# M660A.net
KiCad netlist of a schematic drawn in EAGLE
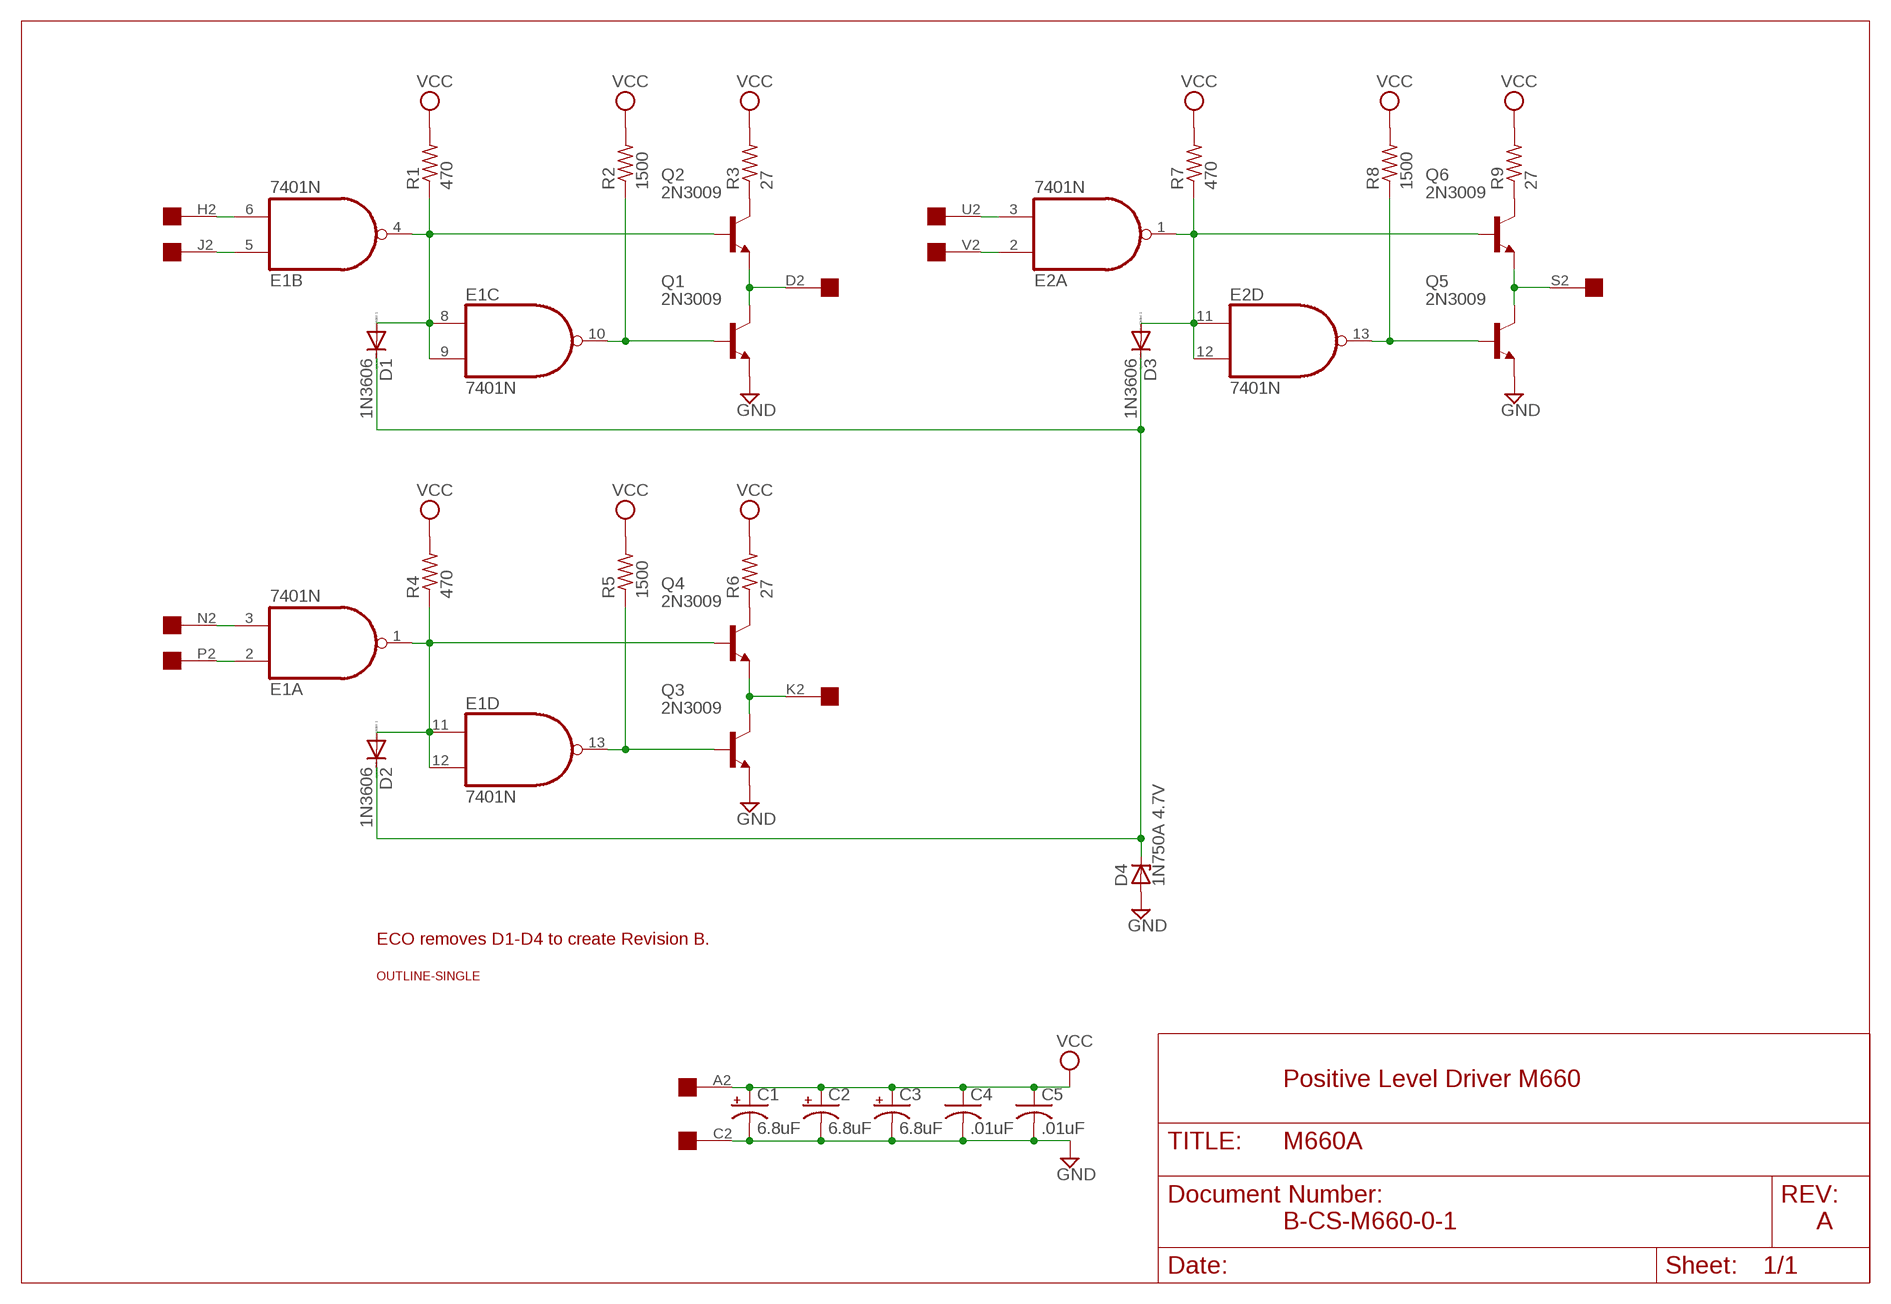
[diagram p0: schematic, sheet 1]

(export (version "E")
  (design (tool "Eeschema 10.0.6"))
  (components
    (comp (ref "C1")
      (value "6.8uF")
      (footprint "eagle-import:E15-5")
      (libsource (lib "eagle-import") (part "CPOL-USE15-5AXIAL"))
    )
    (comp (ref "C2")
      (value "6.8uF")
      (footprint "eagle-import:E15-5")
      (libsource (lib "eagle-import") (part "CPOL-USE15-5AXIAL"))
    )
    (comp (ref "C3")
      (value "6.8uF")
      (footprint "eagle-import:E15-5")
      (libsource (lib "eagle-import") (part "CPOL-USE15-5AXIAL"))
    )
    (comp (ref "C4")
      (value ".01uF")
      (footprint "eagle-import:C050-025X075")
      (libsource (lib "eagle-import") (part "C-US050-025X075"))
    )
    (comp (ref "C5")
      (value ".01uF")
      (footprint "eagle-import:C050-025X075")
      (libsource (lib "eagle-import") (part "C-US050-025X075"))
    )
    (comp (ref "D1")
      (value "1N3606")
      (footprint "eagle-import:DO35-10")
      (libsource (lib "eagle-import") (part "1N4148DO35-10"))
    )
    (comp (ref "D2")
      (value "1N3606")
      (footprint "eagle-import:DO35-10")
      (libsource (lib "eagle-import") (part "1N4148DO35-10"))
    )
    (comp (ref "D3")
      (value "1N3606")
      (footprint "eagle-import:DO35-10")
      (libsource (lib "eagle-import") (part "1N4148DO35-10"))
    )
    (comp (ref "D4")
      (value "1N750A 4.7V")
      (footprint "eagle-import:DO35Z10")
      (libsource (lib "eagle-import") (part "ZENER-DIODEDO35Z10"))
    )
    (comp (ref "E1")
      (value "7401N")
      (footprint "eagle-import:DIL14")
      (libsource (lib "eagle-import") (part "7401NLS"))
    )
    (comp (ref "E2")
      (value "7401N")
      (footprint "eagle-import:DIL14")
      (libsource (lib "eagle-import") (part "7401NLS"))
    )
    (comp (ref "Q1")
      (value "2N3009")
      (footprint "eagle-import:TO5")
      (libsource (lib "eagle-import") (part "2N2219"))
    )
    (comp (ref "Q2")
      (value "2N3009")
      (footprint "eagle-import:TO5")
      (libsource (lib "eagle-import") (part "2N2219"))
    )
    (comp (ref "Q3")
      (value "2N3009")
      (footprint "eagle-import:TO5")
      (libsource (lib "eagle-import") (part "2N2219"))
    )
    (comp (ref "Q4")
      (value "2N3009")
      (footprint "eagle-import:TO5")
      (libsource (lib "eagle-import") (part "2N2219"))
    )
    (comp (ref "Q5")
      (value "2N3009")
      (footprint "eagle-import:TO5")
      (libsource (lib "eagle-import") (part "2N2219"))
    )
    (comp (ref "Q6")
      (value "2N3009")
      (footprint "eagle-import:TO5")
      (libsource (lib "eagle-import") (part "2N2219"))
    )
    (comp (ref "R1")
      (value "470")
      (footprint "eagle-import:0207_10")
      (libsource (lib "eagle-import") (part "R-US_0207/10"))
    )
    (comp (ref "R2")
      (value "1500")
      (footprint "eagle-import:0207_10")
      (libsource (lib "eagle-import") (part "R-US_0207/10"))
    )
    (comp (ref "R3")
      (value "27")
      (footprint "eagle-import:0411_15")
      (libsource (lib "eagle-import") (part "R-US_0411/15"))
    )
    (comp (ref "R4")
      (value "470")
      (footprint "eagle-import:0207_10")
      (libsource (lib "eagle-import") (part "R-US_0207/10"))
    )
    (comp (ref "R5")
      (value "1500")
      (footprint "eagle-import:0207_10")
      (libsource (lib "eagle-import") (part "R-US_0207/10"))
    )
    (comp (ref "R6")
      (value "27")
      (footprint "eagle-import:0411_15")
      (libsource (lib "eagle-import") (part "R-US_0411/15"))
    )
    (comp (ref "R7")
      (value "470")
      (footprint "eagle-import:0207_10")
      (libsource (lib "eagle-import") (part "R-US_0207/10"))
    )
    (comp (ref "R8")
      (value "1500")
      (footprint "eagle-import:0207_10")
      (libsource (lib "eagle-import") (part "R-US_0207/10"))
    )
    (comp (ref "R9")
      (value "27")
      (footprint "eagle-import:0411_15")
      (libsource (lib "eagle-import") (part "R-US_0411/15"))
    )
    (comp (ref "U$1")
      (value "OUTLINE-SINGLE")
      (footprint "eagle-import:SINGLE")
      (libsource (lib "eagle-import") (part "OUTLINE-SINGLE"))
    )
    (comp (ref "U$3")
      (value "EDGE-1")
      (footprint "eagle-import:EDGE-CON1")
      (libsource (lib "eagle-import") (part "EDGE-1"))
    )
  )
  (nets
    (net (code "1") (name "GND") (class "Default")
      (node (ref "C1") (pin "-") (pinfunction "-_-") (pintype "passive"))
      (node (ref "C2") (pin "-") (pinfunction "-_-") (pintype "passive"))
      (node (ref "C3") (pin "-") (pinfunction "-_-") (pintype "passive"))
      (node (ref "C4") (pin "2") (pinfunction "2_2") (pintype "passive"))
      (node (ref "C5") (pin "2") (pinfunction "2_2") (pintype "passive"))
      (node (ref "D4") (pin "A") (pinfunction "A_A") (pintype "passive"))
      (node (ref "Q1") (pin "1") (pinfunction "E_1") (pintype "passive"))
      (node (ref "Q3") (pin "1") (pinfunction "E_1") (pintype "passive"))
      (node (ref "Q5") (pin "1") (pinfunction "E_1") (pintype "passive"))
      (node (ref "U$3") (pin "C2") (pinfunction "1_C2") (pintype "bidirectional"))
    )
    (net (code "2") (name "Net-(D1-PadC)") (class "Default")
      (node (ref "D1") (pin "C") (pinfunction "C_C") (pintype "passive"))
      (node (ref "D2") (pin "C") (pinfunction "C_C") (pintype "passive"))
      (node (ref "D3") (pin "C") (pinfunction "C_C") (pintype "passive"))
      (node (ref "D4") (pin "C") (pinfunction "C_C") (pintype "passive"))
    )
    (net (code "3") (name "Net-(E1A-I0)") (class "Default")
      (node (ref "E1") (pin "2") (pinfunction "I0_2") (pintype "input"))
      (node (ref "U$3") (pin "P2") (pinfunction "1_P2") (pintype "bidirectional"))
    )
    (net (code "4") (name "Net-(E1A-I1)") (class "Default")
      (node (ref "E1") (pin "3") (pinfunction "I1_3") (pintype "input"))
      (node (ref "U$3") (pin "N2") (pinfunction "1_N2") (pintype "bidirectional"))
    )
    (net (code "5") (name "Net-(E1A-O)") (class "Default")
      (node (ref "D2") (pin "A") (pinfunction "A_A") (pintype "passive"))
      (node (ref "E1") (pin "1") (pinfunction "O_1") (pintype "open_collector"))
      (node (ref "E1") (pin "11") (pinfunction "I0_11") (pintype "input"))
      (node (ref "E1") (pin "12") (pinfunction "I1_12") (pintype "input"))
      (node (ref "Q4") (pin "2") (pinfunction "B_2") (pintype "passive"))
      (node (ref "R4") (pin "1") (pinfunction "1_1") (pintype "passive"))
    )
    (net (code "6") (name "Net-(E1B-I0)") (class "Default")
      (node (ref "E1") (pin "5") (pinfunction "I0_5") (pintype "input"))
      (node (ref "U$3") (pin "J2") (pinfunction "1_J2") (pintype "bidirectional"))
    )
    (net (code "7") (name "Net-(E1B-I1)") (class "Default")
      (node (ref "E1") (pin "6") (pinfunction "I1_6") (pintype "input"))
      (node (ref "U$3") (pin "H2") (pinfunction "1_H2") (pintype "bidirectional"))
    )
    (net (code "8") (name "Net-(E1B-O)") (class "Default")
      (node (ref "D1") (pin "A") (pinfunction "A_A") (pintype "passive"))
      (node (ref "E1") (pin "4") (pinfunction "O_4") (pintype "open_collector"))
      (node (ref "E1") (pin "8") (pinfunction "I0_8") (pintype "input"))
      (node (ref "E1") (pin "9") (pinfunction "I1_9") (pintype "input"))
      (node (ref "Q2") (pin "2") (pinfunction "B_2") (pintype "passive"))
      (node (ref "R1") (pin "1") (pinfunction "1_1") (pintype "passive"))
    )
    (net (code "9") (name "Net-(E1C-O)") (class "Default")
      (node (ref "E1") (pin "10") (pinfunction "O_10") (pintype "open_collector"))
      (node (ref "Q1") (pin "2") (pinfunction "B_2") (pintype "passive"))
      (node (ref "R2") (pin "1") (pinfunction "1_1") (pintype "passive"))
    )
    (net (code "10") (name "Net-(E1D-O)") (class "Default")
      (node (ref "E1") (pin "13") (pinfunction "O_13") (pintype "open_collector"))
      (node (ref "Q3") (pin "2") (pinfunction "B_2") (pintype "passive"))
      (node (ref "R5") (pin "1") (pinfunction "1_1") (pintype "passive"))
    )
    (net (code "11") (name "Net-(E2A-I0)") (class "Default")
      (node (ref "E2") (pin "2") (pinfunction "I0_2") (pintype "input"))
      (node (ref "U$3") (pin "V2") (pinfunction "1_V2") (pintype "bidirectional"))
    )
    (net (code "12") (name "Net-(E2A-I1)") (class "Default")
      (node (ref "E2") (pin "3") (pinfunction "I1_3") (pintype "input"))
      (node (ref "U$3") (pin "U2") (pinfunction "1_U2") (pintype "bidirectional"))
    )
    (net (code "13") (name "Net-(E2A-O)") (class "Default")
      (node (ref "D3") (pin "A") (pinfunction "A_A") (pintype "passive"))
      (node (ref "E2") (pin "1") (pinfunction "O_1") (pintype "open_collector"))
      (node (ref "E2") (pin "11") (pinfunction "I0_11") (pintype "input"))
      (node (ref "E2") (pin "12") (pinfunction "I1_12") (pintype "input"))
      (node (ref "Q6") (pin "2") (pinfunction "B_2") (pintype "passive"))
      (node (ref "R7") (pin "1") (pinfunction "1_1") (pintype "passive"))
    )
    (net (code "14") (name "Net-(E2D-O)") (class "Default")
      (node (ref "E2") (pin "13") (pinfunction "O_13") (pintype "open_collector"))
      (node (ref "Q5") (pin "2") (pinfunction "B_2") (pintype "passive"))
      (node (ref "R8") (pin "1") (pinfunction "1_1") (pintype "passive"))
    )
    (net (code "15") (name "Net-(Q1-C)") (class "Default")
      (node (ref "Q1") (pin "3") (pinfunction "C_3") (pintype "passive"))
      (node (ref "Q2") (pin "1") (pinfunction "E_1") (pintype "passive"))
      (node (ref "U$3") (pin "D2") (pinfunction "1_D2") (pintype "bidirectional"))
    )
    (net (code "16") (name "Net-(Q2-C)") (class "Default")
      (node (ref "Q2") (pin "3") (pinfunction "C_3") (pintype "passive"))
      (node (ref "R3") (pin "1") (pinfunction "1_1") (pintype "passive"))
    )
    (net (code "17") (name "Net-(Q3-C)") (class "Default")
      (node (ref "Q3") (pin "3") (pinfunction "C_3") (pintype "passive"))
      (node (ref "Q4") (pin "1") (pinfunction "E_1") (pintype "passive"))
      (node (ref "U$3") (pin "K2") (pinfunction "1_K2") (pintype "bidirectional"))
    )
    (net (code "18") (name "Net-(Q4-C)") (class "Default")
      (node (ref "Q4") (pin "3") (pinfunction "C_3") (pintype "passive"))
      (node (ref "R6") (pin "1") (pinfunction "1_1") (pintype "passive"))
    )
    (net (code "19") (name "Net-(Q5-C)") (class "Default")
      (node (ref "Q5") (pin "3") (pinfunction "C_3") (pintype "passive"))
      (node (ref "Q6") (pin "1") (pinfunction "E_1") (pintype "passive"))
      (node (ref "U$3") (pin "S2") (pinfunction "1_S2") (pintype "bidirectional"))
    )
    (net (code "20") (name "Net-(Q6-C)") (class "Default")
      (node (ref "Q6") (pin "3") (pinfunction "C_3") (pintype "passive"))
      (node (ref "R9") (pin "1") (pinfunction "1_1") (pintype "passive"))
    )
    (net (code "21") (name "VCC") (class "Default")
      (node (ref "C1") (pin "+") (pinfunction "+_+") (pintype "passive"))
      (node (ref "C2") (pin "+") (pinfunction "+_+") (pintype "passive"))
      (node (ref "C3") (pin "+") (pinfunction "+_+") (pintype "passive"))
      (node (ref "C4") (pin "1") (pinfunction "1_1") (pintype "passive"))
      (node (ref "C5") (pin "1") (pinfunction "1_1") (pintype "passive"))
      (node (ref "R1") (pin "2") (pinfunction "2_2") (pintype "passive"))
      (node (ref "R2") (pin "2") (pinfunction "2_2") (pintype "passive"))
      (node (ref "R3") (pin "2") (pinfunction "2_2") (pintype "passive"))
      (node (ref "R4") (pin "2") (pinfunction "2_2") (pintype "passive"))
      (node (ref "R5") (pin "2") (pinfunction "2_2") (pintype "passive"))
      (node (ref "R6") (pin "2") (pinfunction "2_2") (pintype "passive"))
      (node (ref "R7") (pin "2") (pinfunction "2_2") (pintype "passive"))
      (node (ref "R8") (pin "2") (pinfunction "2_2") (pintype "passive"))
      (node (ref "R9") (pin "2") (pinfunction "2_2") (pintype "passive"))
      (node (ref "U$3") (pin "A2") (pinfunction "1_A2") (pintype "bidirectional"))
    )
  )
)
